# micro_RevA.net
KiCad netlist of a schematic drawn in EAGLE
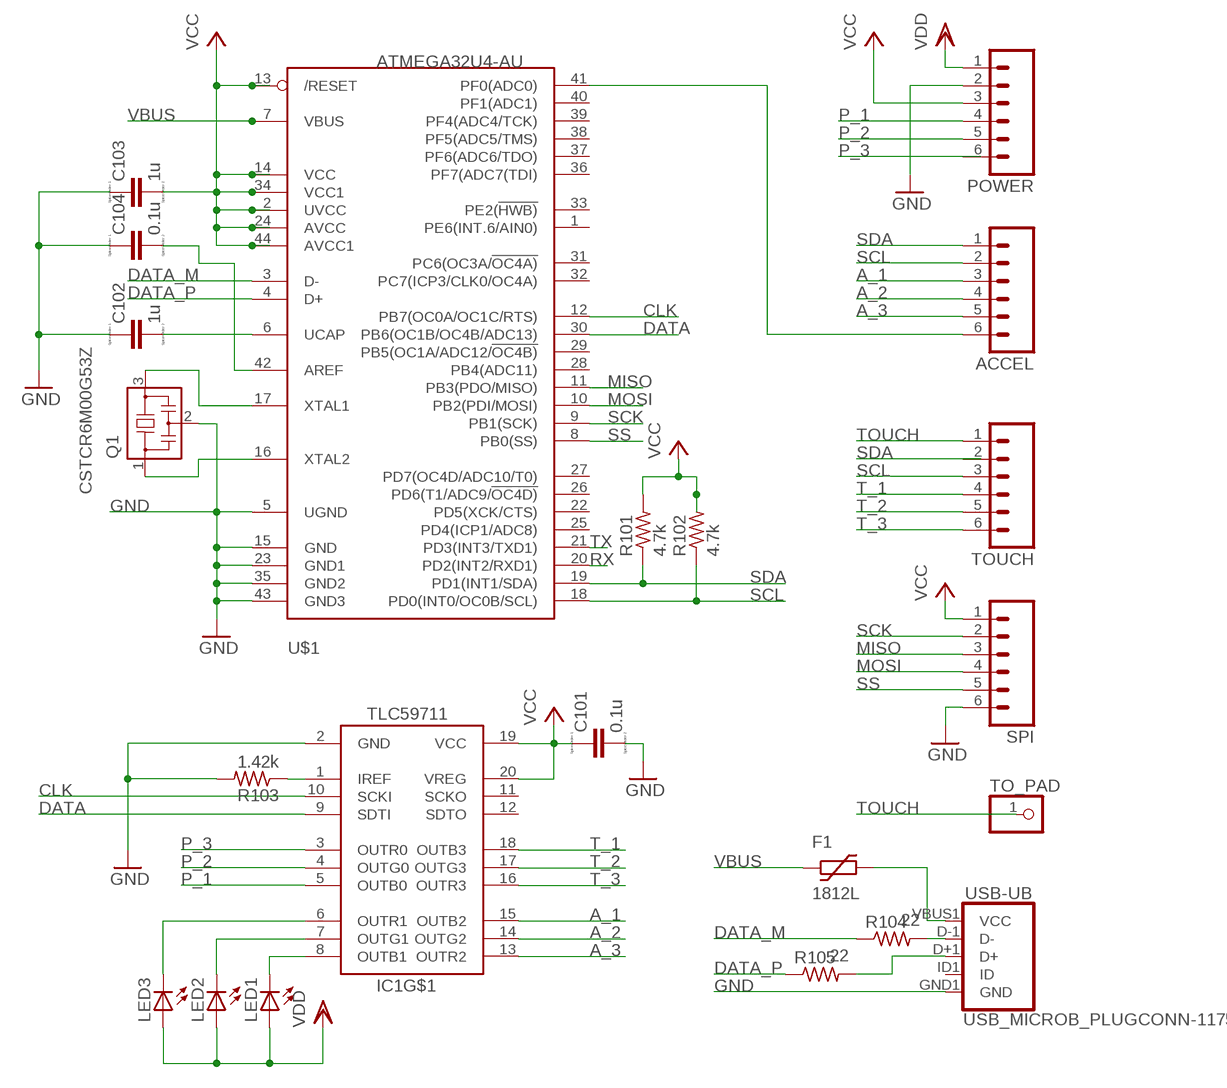
[diagram p0: schematic, sheet 1]

(export (version "E")
  (design (tool "Eeschema 10.0.6"))
  (components
    (comp (ref "ACCEL")
      (value "M06SMD-STRAIGHT-ALT")
      (footprint "eagle-import:1X06_SMD_STRAIGHT_ALT")
      (libsource (lib "eagle-import") (part "M06SMD-STRAIGHT-ALT"))
    )
    (comp (ref "C101")
      (value "0.1u")
      (footprint "eagle-import:C0603")
      (libsource (lib "eagle-import") (part "CC0603"))
    )
    (comp (ref "C102")
      (value "1u")
      (footprint "eagle-import:C0603")
      (libsource (lib "eagle-import") (part "CC0603"))
    )
    (comp (ref "C103")
      (value "1u")
      (footprint "eagle-import:C0603")
      (libsource (lib "eagle-import") (part "CC0603"))
    )
    (comp (ref "C104")
      (value "0.1u")
      (footprint "eagle-import:C0603")
      (libsource (lib "eagle-import") (part "CC0603"))
    )
    (comp (ref "F1")
      (value "1812L")
      (footprint "eagle-import:1812L")
      (libsource (lib "eagle-import") (part "1812L"))
    )
    (comp (ref "IC1")
      (value "TLC59711")
      (footprint "eagle-import:HTSSOP20DAP")
      (libsource (lib "eagle-import") (part "TLC59711"))
    )
    (comp (ref "LED1")
      (value "LEDP-LCC-4")
      (footprint "eagle-import:P-LCC-4")
      (libsource (lib "eagle-import") (part "LEDP-LCC-4"))
    )
    (comp (ref "LED2")
      (value "LEDP-LCC-4")
      (footprint "eagle-import:P-LCC-4")
      (libsource (lib "eagle-import") (part "LEDP-LCC-4"))
    )
    (comp (ref "LED3")
      (value "LEDP-LCC-4")
      (footprint "eagle-import:P-LCC-4")
      (libsource (lib "eagle-import") (part "LEDP-LCC-4"))
    )
    (comp (ref "POWER")
      (value "M06SMD-STRAIGHT-ALT")
      (footprint "eagle-import:1X06_SMD_STRAIGHT_ALT")
      (libsource (lib "eagle-import") (part "M06SMD-STRAIGHT-ALT"))
    )
    (comp (ref "Q1")
      (value "CSTCR6M00G53Z")
      (footprint "eagle-import:CSTCR6M")
      (fields (field (name "MPN") "CSTCR6M00G53-R0"))
      (libsource (lib "eagle-import") (part "CSTCR6M00G53Z"))
    )
    (comp (ref "R101")
      (value "4.7k")
      (footprint "eagle-import:R0603")
      (libsource (lib "eagle-import") (part "R-US_R0603"))
    )
    (comp (ref "R102")
      (value "4.7k")
      (footprint "eagle-import:R0603")
      (libsource (lib "eagle-import") (part "R-US_R0603"))
    )
    (comp (ref "R103")
      (value "1.42k")
      (footprint "eagle-import:R0603")
      (libsource (lib "eagle-import") (part "R-US_R0603"))
    )
    (comp (ref "R104")
      (value "22")
      (footprint "eagle-import:R0603")
      (libsource (lib "eagle-import") (part "R-US_R0603"))
    )
    (comp (ref "R105")
      (value "22")
      (footprint "eagle-import:R0603")
      (libsource (lib "eagle-import") (part "R-US_R0603"))
    )
    (comp (ref "SPI")
      (value "M06SMD-STRAIGHT-ALT")
      (footprint "eagle-import:1X06_SMD_STRAIGHT_ALT")
      (libsource (lib "eagle-import") (part "M06SMD-STRAIGHT-ALT"))
    )
    (comp (ref "TOUCH")
      (value "M06SMD-STRAIGHT-ALT")
      (footprint "eagle-import:1X06_SMD_STRAIGHT_ALT")
      (libsource (lib "eagle-import") (part "M06SMD-STRAIGHT-ALT"))
    )
    (comp (ref "TO_PAD")
      (value "PINHD-1X1")
      (footprint "eagle-import:1X01")
      (libsource (lib "eagle-import") (part "PINHD-1X1"))
    )
    (comp (ref "U$1")
      (value "ATMEGA32U4-AU")
      (footprint "eagle-import:TQFP44")
      (libsource (lib "eagle-import") (part "ATMEGA32U4-AU"))
    )
    (comp (ref "USB-UB")
      (value "USB_MICROB_PLUGCONN-11752")
      (footprint "eagle-import:USB-B-MICRO-SMD_V03")
      (libsource (lib "eagle-import") (part "USB_MICROB_PLUGCONN-11752"))
    )
  )
  (nets
    (net (code "1") (name "/A_1") (class "Default")
      (node (ref "ACCEL") (pin "3") (pinfunction "3_3") (pintype "passive"))
      (node (ref "IC1") (pin "15") (pinfunction "OUTB2_15") (pintype "open_collector"))
    )
    (net (code "2") (name "/A_2") (class "Default")
      (node (ref "ACCEL") (pin "4") (pinfunction "4_4") (pintype "passive"))
      (node (ref "IC1") (pin "14") (pinfunction "OUTG2_14") (pintype "open_collector"))
    )
    (net (code "3") (name "/A_3") (class "Default")
      (node (ref "ACCEL") (pin "5") (pinfunction "5_5") (pintype "passive"))
      (node (ref "IC1") (pin "13") (pinfunction "OUTR2_13") (pintype "open_collector"))
    )
    (net (code "4") (name "/CLK") (class "Default")
      (node (ref "IC1") (pin "10") (pinfunction "SCKI_10") (pintype "input"))
      (node (ref "U$1") (pin "12") (pinfunction "PB7(OC0A/OC1C/RTS)_12") (pintype "bidirectional"))
    )
    (net (code "5") (name "/DATA") (class "Default")
      (node (ref "IC1") (pin "9") (pinfunction "SDTI_9") (pintype "input"))
      (node (ref "U$1") (pin "30") (pinfunction "PB6(OC1B/OC4B/ADC13)_30") (pintype "bidirectional"))
    )
    (net (code "6") (name "/DATA_M") (class "Default")
      (node (ref "R104") (pin "1") (pinfunction "1_1") (pintype "passive"))
      (node (ref "U$1") (pin "3") (pinfunction "D-_3") (pintype "bidirectional"))
    )
    (net (code "7") (name "/DATA_P") (class "Default")
      (node (ref "R105") (pin "1") (pinfunction "1_1") (pintype "passive"))
      (node (ref "U$1") (pin "4") (pinfunction "D+_4") (pintype "bidirectional"))
    )
    (net (code "8") (name "/MISO") (class "Default")
      (node (ref "SPI") (pin "3") (pinfunction "3_3") (pintype "passive"))
      (node (ref "U$1") (pin "11") (pinfunction "PB3(PDO/MISO)_11") (pintype "bidirectional"))
    )
    (net (code "9") (name "/MOSI") (class "Default")
      (node (ref "SPI") (pin "4") (pinfunction "4_4") (pintype "passive"))
      (node (ref "U$1") (pin "10") (pinfunction "PB2(PDI/MOSI)_10") (pintype "bidirectional"))
    )
    (net (code "10") (name "/P_1") (class "Default")
      (node (ref "IC1") (pin "5") (pinfunction "OUTB0_5") (pintype "open_collector"))
      (node (ref "POWER") (pin "4") (pinfunction "4_4") (pintype "passive"))
    )
    (net (code "11") (name "/P_2") (class "Default")
      (node (ref "IC1") (pin "4") (pinfunction "OUTG0_4") (pintype "open_collector"))
      (node (ref "POWER") (pin "5") (pinfunction "5_5") (pintype "passive"))
    )
    (net (code "12") (name "/P_3") (class "Default")
      (node (ref "IC1") (pin "3") (pinfunction "OUTR0_3") (pintype "open_collector"))
      (node (ref "POWER") (pin "6") (pinfunction "6_6") (pintype "passive"))
    )
    (net (code "13") (name "/RX") (class "Default")
      (node (ref "U$1") (pin "20") (pinfunction "PD2(INT2/RXD1)_20") (pintype "bidirectional"))
    )
    (net (code "14") (name "/SCK") (class "Default")
      (node (ref "SPI") (pin "2") (pinfunction "2_2") (pintype "passive"))
      (node (ref "U$1") (pin "9") (pinfunction "PB1(SCK)_9") (pintype "bidirectional"))
    )
    (net (code "15") (name "/SCL") (class "Default")
      (node (ref "ACCEL") (pin "2") (pinfunction "2_2") (pintype "passive"))
      (node (ref "R102") (pin "1") (pinfunction "1_1") (pintype "passive"))
      (node (ref "TOUCH") (pin "3") (pinfunction "3_3") (pintype "passive"))
      (node (ref "U$1") (pin "18") (pinfunction "PD0(INT0/OC0B/SCL)_18") (pintype "bidirectional"))
    )
    (net (code "16") (name "/SDA") (class "Default")
      (node (ref "ACCEL") (pin "1") (pinfunction "1_1") (pintype "passive"))
      (node (ref "R101") (pin "1") (pinfunction "1_1") (pintype "passive"))
      (node (ref "TOUCH") (pin "2") (pinfunction "2_2") (pintype "passive"))
      (node (ref "U$1") (pin "19") (pinfunction "PD1(INT1/SDA)_19") (pintype "bidirectional"))
    )
    (net (code "17") (name "/SS") (class "Default")
      (node (ref "SPI") (pin "5") (pinfunction "5_5") (pintype "passive"))
      (node (ref "U$1") (pin "8") (pinfunction "PB0(SS)_8") (pintype "bidirectional"))
    )
    (net (code "18") (name "/TOUCH") (class "Default")
      (node (ref "TOUCH") (pin "1") (pinfunction "1_1") (pintype "passive"))
      (node (ref "TO_PAD") (pin "1") (pinfunction "1_1") (pintype "passive"))
    )
    (net (code "19") (name "/TX") (class "Default")
      (node (ref "U$1") (pin "21") (pinfunction "PD3(INT3/TXD1)_21") (pintype "bidirectional"))
    )
    (net (code "20") (name "/T_1") (class "Default")
      (node (ref "IC1") (pin "18") (pinfunction "OUTB3_18") (pintype "open_collector"))
      (node (ref "TOUCH") (pin "4") (pinfunction "4_4") (pintype "passive"))
    )
    (net (code "21") (name "/T_2") (class "Default")
      (node (ref "IC1") (pin "17") (pinfunction "OUTG3_17") (pintype "open_collector"))
      (node (ref "TOUCH") (pin "5") (pinfunction "5_5") (pintype "passive"))
    )
    (net (code "22") (name "/T_3") (class "Default")
      (node (ref "IC1") (pin "16") (pinfunction "OUTR3_16") (pintype "open_collector"))
      (node (ref "TOUCH") (pin "6") (pinfunction "6_6") (pintype "passive"))
    )
    (net (code "23") (name "/VBUS") (class "Default")
      (node (ref "F1") (pin "P$1") (pinfunction "1_P$1") (pintype "passive"))
      (node (ref "U$1") (pin "7") (pinfunction "VBUS_7") (pintype "bidirectional"))
    )
    (net (code "24") (name "GND") (class "Default")
      (node (ref "C101") (pin "2") (pinfunction "2_2") (pintype "passive"))
      (node (ref "C102") (pin "1") (pinfunction "1_1") (pintype "passive"))
      (node (ref "C103") (pin "1") (pinfunction "1_1") (pintype "passive"))
      (node (ref "C104") (pin "1") (pinfunction "1_1") (pintype "passive"))
      (node (ref "IC1") (pin "2") (pinfunction "GND_2") (pintype "power_in"))
      (node (ref "POWER") (pin "2") (pinfunction "2_2") (pintype "passive"))
      (node (ref "Q1") (pin "2") (pinfunction "2_2") (pintype "passive"))
      (node (ref "R103") (pin "2") (pinfunction "2_2") (pintype "passive"))
      (node (ref "SPI") (pin "6") (pinfunction "6_6") (pintype "passive"))
      (node (ref "U$1") (pin "15") (pinfunction "GND_15") (pintype "bidirectional"))
      (node (ref "U$1") (pin "23") (pinfunction "GND1_23") (pintype "bidirectional"))
      (node (ref "U$1") (pin "35") (pinfunction "GND2_35") (pintype "bidirectional"))
      (node (ref "U$1") (pin "43") (pinfunction "GND3_43") (pintype "bidirectional"))
      (node (ref "U$1") (pin "5") (pinfunction "UGND_5") (pintype "bidirectional"))
      (node (ref "USB-UB") (pin "GND1") (pinfunction "GND_GND1") (pintype "bidirectional"))
    )
    (net (code "25") (name "Net-(F1-2)") (class "Default")
      (node (ref "F1") (pin "P$2") (pinfunction "2_P$2") (pintype "passive"))
      (node (ref "USB-UB") (pin "VBUS1") (pinfunction "VCC_VBUS1") (pintype "bidirectional"))
    )
    (net (code "26") (name "Net-(IC1A-IREF)") (class "Default")
      (node (ref "IC1") (pin "1") (pinfunction "IREF_1") (pintype "bidirectional"))
      (node (ref "R103") (pin "1") (pinfunction "1_1") (pintype "passive"))
    )
    (net (code "27") (name "Net-(IC1A-OUTB1)") (class "Default")
      (node (ref "IC1") (pin "8") (pinfunction "OUTB1_8") (pintype "open_collector"))
      (node (ref "LED1") (pin "C@4") (pinfunction "C_C@4") (pintype "passive"))
    )
    (net (code "28") (name "Net-(IC1A-OUTG1)") (class "Default")
      (node (ref "IC1") (pin "7") (pinfunction "OUTG1_7") (pintype "open_collector"))
      (node (ref "LED2") (pin "C@4") (pinfunction "C_C@4") (pintype "passive"))
    )
    (net (code "29") (name "Net-(IC1A-OUTR1)") (class "Default")
      (node (ref "IC1") (pin "6") (pinfunction "OUTR1_6") (pintype "open_collector"))
      (node (ref "LED3") (pin "C@4") (pinfunction "C_C@4") (pintype "passive"))
    )
    (net (code "30") (name "Net-(U$1-AREF)") (class "Default")
      (node (ref "C104") (pin "2") (pinfunction "2_2") (pintype "passive"))
      (node (ref "U$1") (pin "42") (pinfunction "AREF_42") (pintype "bidirectional"))
    )
    (net (code "31") (name "Net-(U$1-PF0(ADC0))") (class "Default")
      (node (ref "ACCEL") (pin "6") (pinfunction "6_6") (pintype "passive"))
      (node (ref "U$1") (pin "41") (pinfunction "PF0(ADC0)_41") (pintype "bidirectional"))
    )
    (net (code "32") (name "Net-(U$1-UCAP)") (class "Default")
      (node (ref "C102") (pin "2") (pinfunction "2_2") (pintype "passive"))
      (node (ref "U$1") (pin "6") (pinfunction "UCAP_6") (pintype "bidirectional"))
    )
    (net (code "33") (name "Net-(U$1-XTAL1)") (class "Default")
      (node (ref "Q1") (pin "3") (pinfunction "3_3") (pintype "passive"))
      (node (ref "U$1") (pin "17") (pinfunction "XTAL1_17") (pintype "bidirectional"))
    )
    (net (code "34") (name "Net-(U$1-XTAL2)") (class "Default")
      (node (ref "Q1") (pin "1") (pinfunction "1_1") (pintype "passive"))
      (node (ref "U$1") (pin "16") (pinfunction "XTAL2_16") (pintype "bidirectional"))
    )
    (net (code "35") (name "Net-(USB-UB-D+)") (class "Default")
      (node (ref "R105") (pin "2") (pinfunction "2_2") (pintype "passive"))
      (node (ref "USB-UB") (pin "D+1") (pinfunction "D+_D+1") (pintype "bidirectional"))
    )
    (net (code "36") (name "Net-(USB-UB-D-)") (class "Default")
      (node (ref "R104") (pin "2") (pinfunction "2_2") (pintype "passive"))
      (node (ref "USB-UB") (pin "D-1") (pinfunction "D-_D-1") (pintype "bidirectional"))
    )
    (net (code "37") (name "VCC") (class "Default")
      (node (ref "C101") (pin "1") (pinfunction "1_1") (pintype "passive"))
      (node (ref "C103") (pin "2") (pinfunction "2_2") (pintype "passive"))
      (node (ref "IC1") (pin "19") (pinfunction "VCC_19") (pintype "power_in"))
      (node (ref "IC1") (pin "20") (pinfunction "VREG_20") (pintype "bidirectional"))
      (node (ref "POWER") (pin "3") (pinfunction "3_3") (pintype "passive"))
      (node (ref "R101") (pin "2") (pinfunction "2_2") (pintype "passive"))
      (node (ref "R102") (pin "2") (pinfunction "2_2") (pintype "passive"))
      (node (ref "SPI") (pin "1") (pinfunction "1_1") (pintype "passive"))
      (node (ref "U$1") (pin "13") (pinfunction "/RESET_13") (pintype "bidirectional"))
      (node (ref "U$1") (pin "14") (pinfunction "VCC_14") (pintype "bidirectional"))
      (node (ref "U$1") (pin "2") (pinfunction "UVCC_2") (pintype "bidirectional"))
      (node (ref "U$1") (pin "24") (pinfunction "AVCC_24") (pintype "bidirectional"))
      (node (ref "U$1") (pin "34") (pinfunction "VCC1_34") (pintype "bidirectional"))
      (node (ref "U$1") (pin "44") (pinfunction "AVCC1_44") (pintype "bidirectional"))
    )
    (net (code "38") (name "VDD") (class "Default")
      (node (ref "LED1") (pin "A") (pinfunction "A_A") (pintype "passive"))
      (node (ref "LED2") (pin "A") (pinfunction "A_A") (pintype "passive"))
      (node (ref "LED3") (pin "A") (pinfunction "A_A") (pintype "passive"))
      (node (ref "POWER") (pin "1") (pinfunction "1_1") (pintype "passive"))
    )
    (net (code "39") (name "unconnected-(IC1A-SCKO-Pad11)") (class "Default")
      (node (ref "IC1") (pin "11") (pinfunction "SCKO_11") (pintype "output"))
    )
    (net (code "40") (name "unconnected-(IC1A-SDTO-Pad12)") (class "Default")
      (node (ref "IC1") (pin "12") (pinfunction "SDTO_12") (pintype "output"))
    )
    (net (code "41") (name "unconnected-(U$1-PB4(ADC11)-Pad28)") (class "Default")
      (node (ref "U$1") (pin "28") (pinfunction "PB4(ADC11)_28") (pintype "bidirectional"))
    )
    (net (code "42") (name "unconnected-(U$1-PB5(OC1A{slash}ADC12{slash}~{OC4B})-Pad29)") (class "Default")
      (node (ref "U$1") (pin "29") (pinfunction "PB5(OC1A/ADC12/~{OC4B})_29") (pintype "bidirectional"))
    )
    (net (code "43") (name "unconnected-(U$1-PC6(OC3A{slash}~{OC4A})-Pad31)") (class "Default")
      (node (ref "U$1") (pin "31") (pinfunction "PC6(OC3A/~{OC4A})_31") (pintype "bidirectional"))
    )
    (net (code "44") (name "unconnected-(U$1-PC7(ICP3{slash}CLK0{slash}OC4A)-Pad32)") (class "Default")
      (node (ref "U$1") (pin "32") (pinfunction "PC7(ICP3/CLK0/OC4A)_32") (pintype "bidirectional"))
    )
    (net (code "45") (name "unconnected-(U$1-PD4(ICP1{slash}ADC8)-Pad25)") (class "Default")
      (node (ref "U$1") (pin "25") (pinfunction "PD4(ICP1/ADC8)_25") (pintype "bidirectional"))
    )
    (net (code "46") (name "unconnected-(U$1-PD5(XCK{slash}CTS)-Pad22)") (class "Default")
      (node (ref "U$1") (pin "22") (pinfunction "PD5(XCK/CTS)_22") (pintype "bidirectional"))
    )
    (net (code "47") (name "unconnected-(U$1-PD6(T1{slash}ADC9{slash}~{OC4D})-Pad26)") (class "Default")
      (node (ref "U$1") (pin "26") (pinfunction "PD6(T1/ADC9/~{OC4D})_26") (pintype "bidirectional"))
    )
    (net (code "48") (name "unconnected-(U$1-PD7(OC4D{slash}ADC10{slash}T0)-Pad27)") (class "Default")
      (node (ref "U$1") (pin "27") (pinfunction "PD7(OC4D/ADC10/T0)_27") (pintype "bidirectional"))
    )
    (net (code "49") (name "unconnected-(U$1-PE2(~{HWB})-Pad33)") (class "Default")
      (node (ref "U$1") (pin "33") (pinfunction "PE2(~{HWB})_33") (pintype "bidirectional"))
    )
    (net (code "50") (name "unconnected-(U$1-PE6(INT.6{slash}AIN0)-Pad1)") (class "Default")
      (node (ref "U$1") (pin "1") (pinfunction "PE6(INT.6/AIN0)_1") (pintype "bidirectional"))
    )
    (net (code "51") (name "unconnected-(U$1-PF1(ADC1)-Pad40)") (class "Default")
      (node (ref "U$1") (pin "40") (pinfunction "PF1(ADC1)_40") (pintype "bidirectional"))
    )
    (net (code "52") (name "unconnected-(U$1-PF4(ADC4{slash}TCK)-Pad39)") (class "Default")
      (node (ref "U$1") (pin "39") (pinfunction "PF4(ADC4/TCK)_39") (pintype "bidirectional"))
    )
    (net (code "53") (name "unconnected-(U$1-PF5(ADC5{slash}TMS)-Pad38)") (class "Default")
      (node (ref "U$1") (pin "38") (pinfunction "PF5(ADC5/TMS)_38") (pintype "bidirectional"))
    )
    (net (code "54") (name "unconnected-(U$1-PF6(ADC6{slash}TDO)-Pad37)") (class "Default")
      (node (ref "U$1") (pin "37") (pinfunction "PF6(ADC6/TDO)_37") (pintype "bidirectional"))
    )
    (net (code "55") (name "unconnected-(U$1-PF7(ADC7(TDI)-Pad36)") (class "Default")
      (node (ref "U$1") (pin "36") (pinfunction "PF7(ADC7(TDI)_36") (pintype "bidirectional"))
    )
    (net (code "56") (name "unconnected-(USB-UB-ID-PadID1)") (class "Default")
      (node (ref "USB-UB") (pin "ID1") (pinfunction "ID_ID1") (pintype "bidirectional"))
    )
  )
)
